# untitled-pan.net
KiCad netlist of a schematic drawn in EAGLE
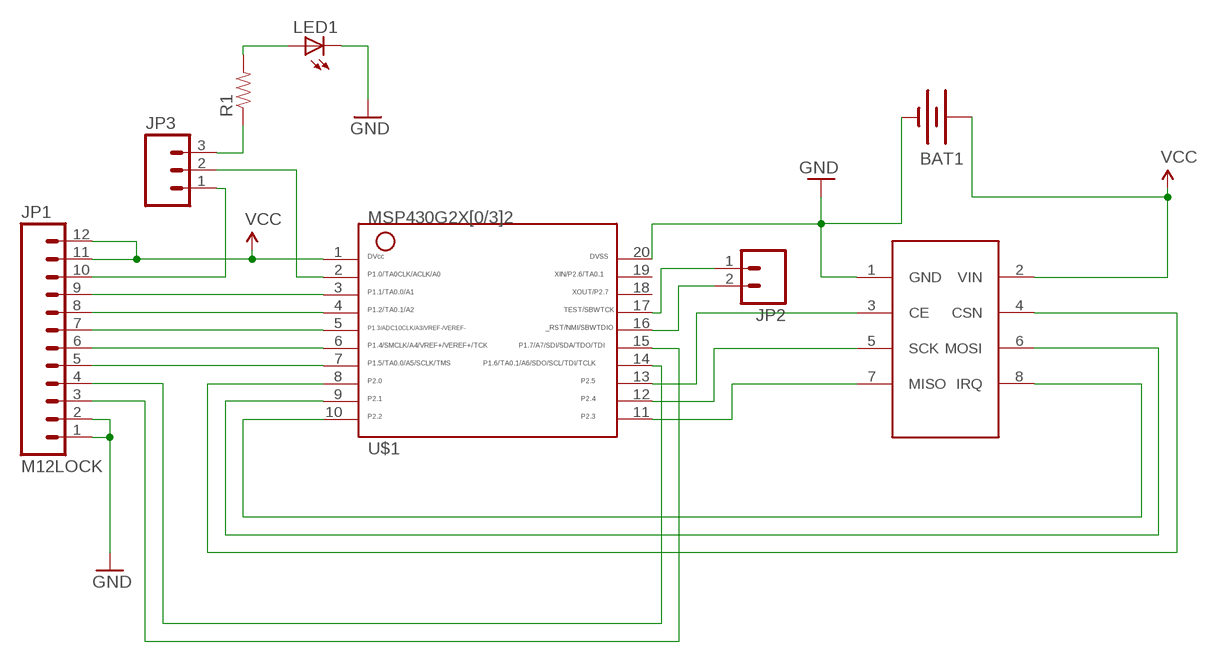
[diagram p0: schematic, sheet 1]

(export (version "E")
  (design (tool "Eeschema 10.0.6"))
  (components
    (comp (ref "BAT1")
      (value "BATTERY20PTH")
      (footprint "eagle-import:BATTCOM_20MM_PTH")
      (libsource (lib "eagle-import") (part "BATTERY20PTH"))
    )
    (comp (ref "JP1")
      (value "M12LOCK")
      (footprint "eagle-import:1X12_LOCK")
      (libsource (lib "eagle-import") (part "M12LOCK"))
    )
    (comp (ref "JP2")
      (value "M02PTH")
      (footprint "eagle-import:1X02")
      (libsource (lib "eagle-import") (part "M02PTH"))
    )
    (comp (ref "JP3")
      (value "M03PTH")
      (footprint "eagle-import:1X03")
      (libsource (lib "eagle-import") (part "M03PTH"))
    )
    (comp (ref "LED1")
      (value "LED3MM")
      (footprint "eagle-import:LED3MM")
      (libsource (lib "eagle-import") (part "LED3MM"))
    )
    (comp (ref "R1")
      (value "RESISTORAXIAL-0.3")
      (footprint "eagle-import:AXIAL-0.3")
      (libsource (lib "eagle-import") (part "RESISTORAXIAL-0.3"))
    )
    (comp (ref "U$1")
      (value "G2X[0/3]2---N20")
      (footprint "eagle-import:N20")
      (libsource (lib "eagle-import") (part "G2X[0/3]2---N20"))
    )
    (comp (ref "U1")
      (value "NRF24L01-4X2")
      (footprint "eagle-import:NRF24L01-4X2")
      (libsource (lib "eagle-import") (part "NRF24L01-4X2"))
    )
  )
  (nets
    (net (code "1") (name "GND") (class "Default")
      (node (ref "BAT1") (pin "2") (pinfunction "-_2") (pintype "power_in"))
      (node (ref "JP1") (pin "1") (pinfunction "1_1") (pintype "passive"))
      (node (ref "JP1") (pin "2") (pinfunction "2_2") (pintype "passive"))
      (node (ref "LED1") (pin "K") (pinfunction "C_K") (pintype "passive"))
      (node (ref "U$1") (pin "20") (pinfunction "20_20") (pintype "bidirectional"))
      (node (ref "U1") (pin "1") (pinfunction "GND_1") (pintype "power_in"))
    )
    (net (code "2") (name "Net-(JP1-Pad3)") (class "Default")
      (node (ref "JP1") (pin "3") (pinfunction "3_3") (pintype "passive"))
      (node (ref "U$1") (pin "15") (pinfunction "15_15") (pintype "bidirectional"))
    )
    (net (code "3") (name "Net-(JP1-Pad4)") (class "Default")
      (node (ref "JP1") (pin "4") (pinfunction "4_4") (pintype "passive"))
      (node (ref "U$1") (pin "14") (pinfunction "14_14") (pintype "bidirectional"))
    )
    (net (code "4") (name "Net-(JP1-Pad5)") (class "Default")
      (node (ref "JP1") (pin "5") (pinfunction "5_5") (pintype "passive"))
      (node (ref "U$1") (pin "7") (pinfunction "7_7") (pintype "bidirectional"))
    )
    (net (code "5") (name "Net-(JP1-Pad6)") (class "Default")
      (node (ref "JP1") (pin "6") (pinfunction "6_6") (pintype "passive"))
      (node (ref "U$1") (pin "6") (pinfunction "6_6") (pintype "bidirectional"))
    )
    (net (code "6") (name "Net-(JP1-Pad7)") (class "Default")
      (node (ref "JP1") (pin "7") (pinfunction "7_7") (pintype "passive"))
      (node (ref "U$1") (pin "5") (pinfunction "5_5") (pintype "bidirectional"))
    )
    (net (code "7") (name "Net-(JP1-Pad8)") (class "Default")
      (node (ref "JP1") (pin "8") (pinfunction "8_8") (pintype "passive"))
      (node (ref "U$1") (pin "4") (pinfunction "4_4") (pintype "bidirectional"))
    )
    (net (code "8") (name "Net-(JP1-Pad9)") (class "Default")
      (node (ref "JP1") (pin "9") (pinfunction "9_9") (pintype "passive"))
      (node (ref "U$1") (pin "3") (pinfunction "3_3") (pintype "bidirectional"))
    )
    (net (code "9") (name "Net-(JP1-Pad10)") (class "Default")
      (node (ref "JP1") (pin "10") (pinfunction "10_10") (pintype "passive"))
      (node (ref "JP3") (pin "1") (pinfunction "1_1") (pintype "passive"))
    )
    (net (code "10") (name "Net-(JP2-Pad1)") (class "Default")
      (node (ref "JP2") (pin "1") (pinfunction "1_1") (pintype "passive"))
      (node (ref "U$1") (pin "17") (pinfunction "17_17") (pintype "bidirectional"))
    )
    (net (code "11") (name "Net-(JP2-Pad2)") (class "Default")
      (node (ref "JP2") (pin "2") (pinfunction "2_2") (pintype "passive"))
      (node (ref "U$1") (pin "16") (pinfunction "16_16") (pintype "bidirectional"))
    )
    (net (code "12") (name "Net-(JP3-Pad2)") (class "Default")
      (node (ref "JP3") (pin "2") (pinfunction "2_2") (pintype "passive"))
      (node (ref "U$1") (pin "2") (pinfunction "2_2") (pintype "bidirectional"))
    )
    (net (code "13") (name "Net-(R1-1)") (class "Default")
      (node (ref "JP3") (pin "3") (pinfunction "3_3") (pintype "passive"))
      (node (ref "R1") (pin "P$1") (pinfunction "1_P$1") (pintype "passive"))
    )
    (net (code "14") (name "Net-(R1-2)") (class "Default")
      (node (ref "LED1") (pin "A") (pinfunction "A_A") (pintype "passive"))
      (node (ref "R1") (pin "P$2") (pinfunction "2_P$2") (pintype "passive"))
    )
    (net (code "15") (name "Net-(U1-CE)") (class "Default")
      (node (ref "U$1") (pin "13") (pinfunction "13_13") (pintype "bidirectional"))
      (node (ref "U1") (pin "3") (pinfunction "CE_3") (pintype "input"))
    )
    (net (code "16") (name "Net-(U1-CSN)") (class "Default")
      (node (ref "U$1") (pin "8") (pinfunction "8_8") (pintype "bidirectional"))
      (node (ref "U1") (pin "4") (pinfunction "CSN_4") (pintype "input"))
    )
    (net (code "17") (name "Net-(U1-IRQ)") (class "Default")
      (node (ref "U$1") (pin "10") (pinfunction "10_10") (pintype "bidirectional"))
      (node (ref "U1") (pin "8") (pinfunction "IRQ_8") (pintype "output"))
    )
    (net (code "18") (name "Net-(U1-MISO)") (class "Default")
      (node (ref "U$1") (pin "11") (pinfunction "11_11") (pintype "bidirectional"))
      (node (ref "U1") (pin "7") (pinfunction "MISO_7") (pintype "output"))
    )
    (net (code "19") (name "Net-(U1-MOSI)") (class "Default")
      (node (ref "U$1") (pin "9") (pinfunction "9_9") (pintype "bidirectional"))
      (node (ref "U1") (pin "6") (pinfunction "MOSI_6") (pintype "input"))
    )
    (net (code "20") (name "Net-(U1-SCK)") (class "Default")
      (node (ref "U$1") (pin "12") (pinfunction "12_12") (pintype "bidirectional"))
      (node (ref "U1") (pin "5") (pinfunction "SCK_5") (pintype "input"))
    )
    (net (code "21") (name "VCC") (class "Default")
      (node (ref "BAT1") (pin "1") (pinfunction "+_1") (pintype "power_in"))
      (node (ref "JP1") (pin "11") (pinfunction "11_11") (pintype "passive"))
      (node (ref "JP1") (pin "12") (pinfunction "12_12") (pintype "passive"))
      (node (ref "U$1") (pin "1") (pinfunction "1_1") (pintype "bidirectional"))
      (node (ref "U1") (pin "2") (pinfunction "VIN_2") (pintype "power_in"))
    )
    (net (code "22") (name "unconnected-(U$1-Pad18)") (class "Default")
      (node (ref "U$1") (pin "18") (pinfunction "18_18") (pintype "bidirectional"))
    )
    (net (code "23") (name "unconnected-(U$1-Pad19)") (class "Default")
      (node (ref "U$1") (pin "19") (pinfunction "19_19") (pintype "bidirectional"))
    )
  )
)
